# bot_uc_board.net
KiCad netlist of a schematic drawn in EAGLE
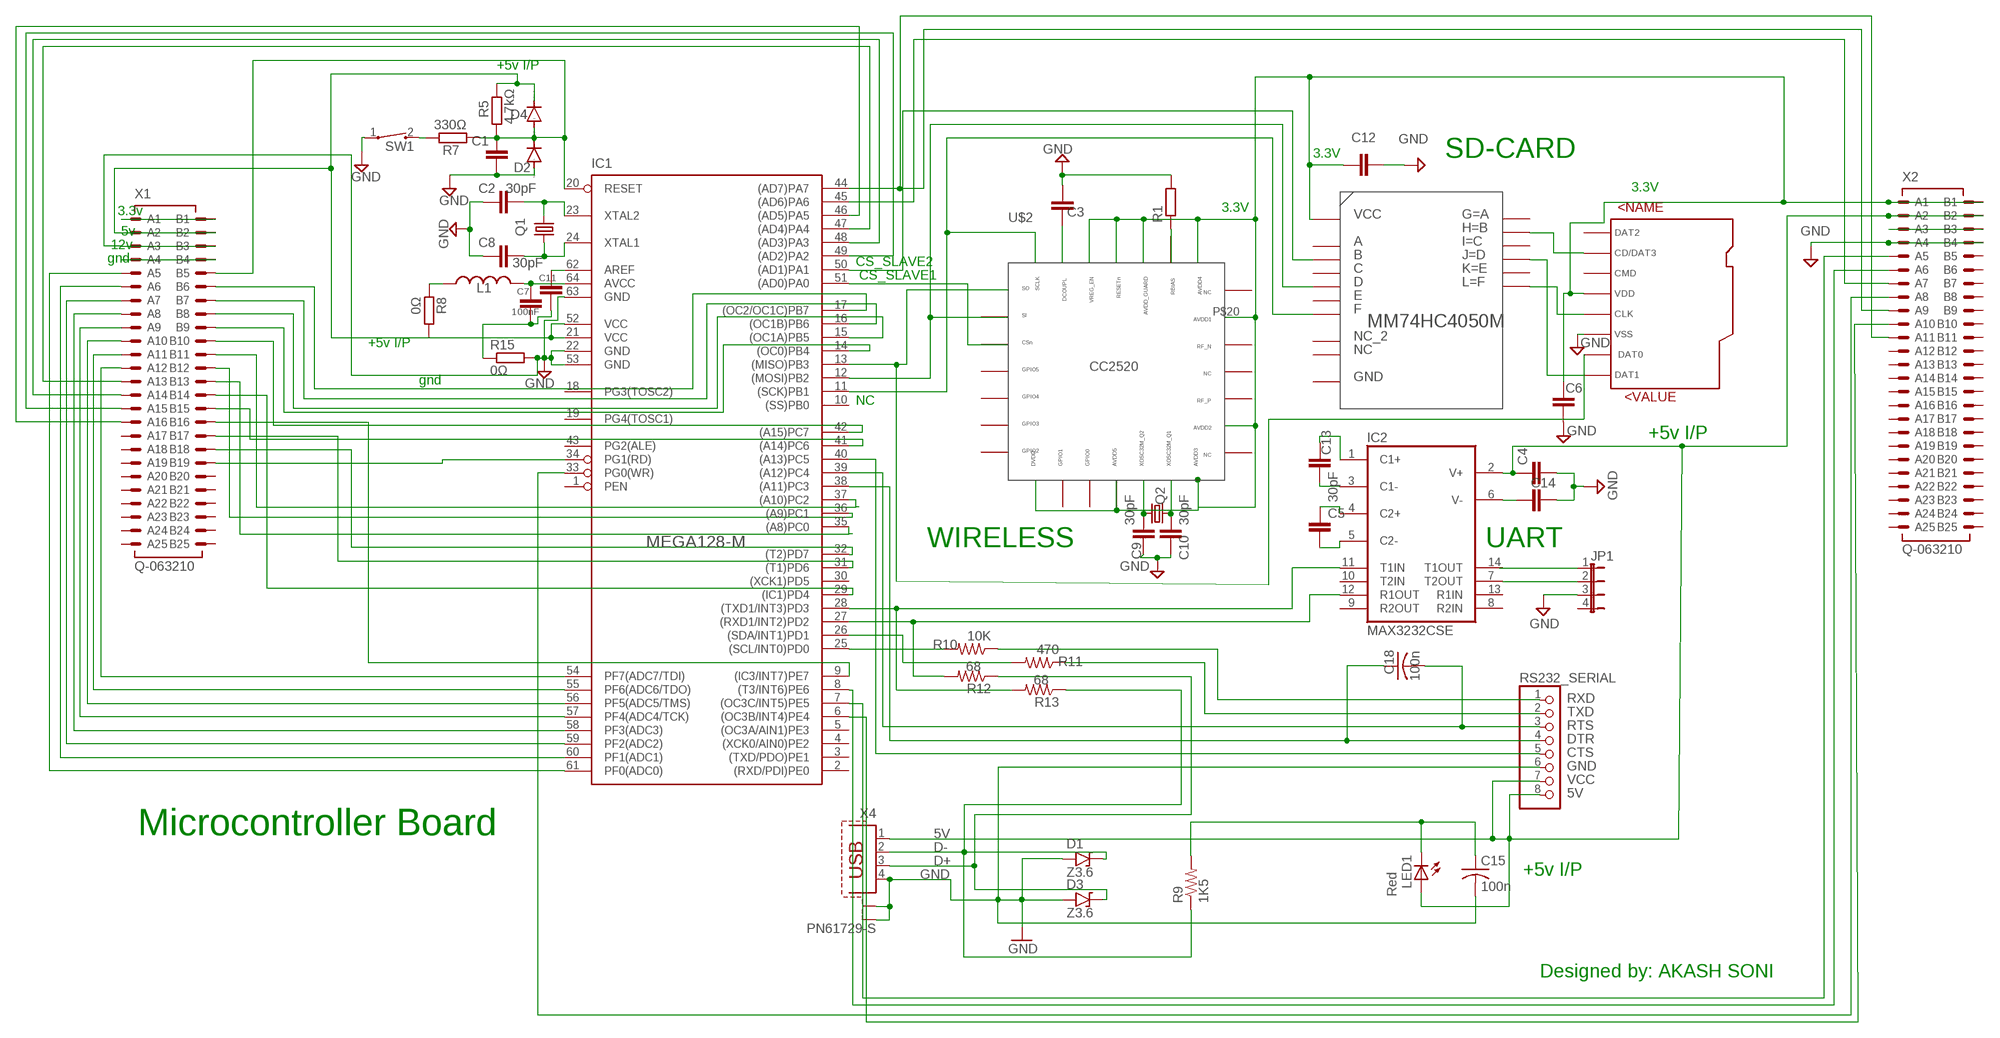
[diagram p0: schematic, sheet 1]

(export (version "E")
  (design (tool "Eeschema 10.0.6"))
  (components
    (comp (ref "C1")
      (value "C-EU025-024X044")
      (footprint "eagle-import:C025-024X044")
      (libsource (lib "eagle-import") (part "C-EU025-024X044"))
    )
    (comp (ref "C2")
      (value "30pF")
      (footprint "eagle-import:C025-024X044")
      (libsource (lib "eagle-import") (part "C-EU025-024X044"))
    )
    (comp (ref "C3")
      (value "C-EU025-024X044")
      (footprint "eagle-import:C025-024X044")
      (libsource (lib "eagle-import") (part "C-EU025-024X044"))
    )
    (comp (ref "C4")
      (value "C-EU025-024X044")
      (footprint "eagle-import:C025-024X044")
      (libsource (lib "eagle-import") (part "C-EU025-024X044"))
    )
    (comp (ref "C5")
      (value "C-EU025-024X044")
      (footprint "eagle-import:C025-024X044")
      (libsource (lib "eagle-import") (part "C-EU025-024X044"))
    )
    (comp (ref "C6")
      (value "30pF")
      (footprint "eagle-import:C025-024X044")
      (libsource (lib "eagle-import") (part "C-EU025-024X044"))
    )
    (comp (ref "C7")
      (value "C-EU025-024X044")
      (footprint "eagle-import:C025-024X044")
      (libsource (lib "eagle-import") (part "C-EU025-024X044"))
    )
    (comp (ref "C8")
      (value "30pF")
      (footprint "eagle-import:C025-024X044")
      (libsource (lib "eagle-import") (part "C-EU025-024X044"))
    )
    (comp (ref "C9")
      (value "30pF")
      (footprint "eagle-import:C025-024X044")
      (libsource (lib "eagle-import") (part "C-EU025-024X044"))
    )
    (comp (ref "C10")
      (value "30pF")
      (footprint "eagle-import:C025-024X044")
      (libsource (lib "eagle-import") (part "C-EU025-024X044"))
    )
    (comp (ref "C11")
      (value "100nF")
      (footprint "eagle-import:C025-024X044")
      (libsource (lib "eagle-import") (part "C-EU025-024X044"))
    )
    (comp (ref "C12")
      (value "C-EU025-024X044")
      (footprint "eagle-import:C025-024X044")
      (libsource (lib "eagle-import") (part "C-EU025-024X044"))
    )
    (comp (ref "C13")
      (value "30pF")
      (footprint "eagle-import:C025-024X044")
      (libsource (lib "eagle-import") (part "C-EU025-024X044"))
    )
    (comp (ref "C14")
      (value "C-EU025-024X044")
      (footprint "eagle-import:C025-024X044")
      (libsource (lib "eagle-import") (part "C-EU025-024X044"))
    )
    (comp (ref "C15")
      (value "100n")
      (footprint "eagle-import:C050-024X044")
      (libsource (lib "eagle-import") (part "C-US050-024X044"))
    )
    (comp (ref "C18")
      (value "100n")
      (footprint "eagle-import:C050-024X044")
      (libsource (lib "eagle-import") (part "C-US050-024X044"))
    )
    (comp (ref "D1")
      (value "Z3.6")
      (footprint "eagle-import:DO35-3")
      (libsource (lib "eagle-import") (part "1N9ZENER"))
    )
    (comp (ref "D2")
      (value "1N4004")
      (footprint "eagle-import:DO41-10")
      (libsource (lib "eagle-import") (part "1N4004"))
    )
    (comp (ref "D3")
      (value "Z3.6")
      (footprint "eagle-import:DO35-3")
      (libsource (lib "eagle-import") (part "1N9ZENER"))
    )
    (comp (ref "D4")
      (value "1N4004")
      (footprint "eagle-import:DO41-10")
      (libsource (lib "eagle-import") (part "1N4004"))
    )
    (comp (ref "IC1")
      (value "MEGA128-M")
      (footprint "eagle-import:MLF64")
      (fields (field (name "MPN") "ATMEGA128-16MU"))
      (libsource (lib "eagle-import") (part "MEGA128-M"))
    )
    (comp (ref "IC2")
      (value "MAX3232CSE")
      (footprint "eagle-import:SO16")
      (libsource (lib "eagle-import") (part "MAX3232SEC"))
    )
    (comp (ref "JP1")
      (value "JP4E")
      (footprint "eagle-import:JP4")
      (libsource (lib "eagle-import") (part "JP4E"))
    )
    (comp (ref "L1")
      (value "L-US0204/5")
      (footprint "eagle-import:0204_5")
      (libsource (lib "eagle-import") (part "L-US0204/5"))
    )
    (comp (ref "LED1")
      (value "Red")
      (footprint "eagle-import:LED3MM")
      (libsource (lib "eagle-import") (part "LED3MM"))
    )
    (comp (ref "Q1")
      (value "CRYSTALHC49U-V")
      (footprint "eagle-import:HC49U-V")
      (libsource (lib "eagle-import") (part "CRYSTALHC49U-V"))
    )
    (comp (ref "Q2")
      (value "CRYSTALHC49U-V")
      (footprint "eagle-import:HC49U-V")
      (libsource (lib "eagle-import") (part "CRYSTALHC49U-V"))
    )
    (comp (ref "R1")
      (value "R-EU_0204/2V")
      (footprint "eagle-import:0204V")
      (libsource (lib "eagle-import") (part "R-EU_0204/2V"))
    )
    (comp (ref "R5")
      (value "4.7kΩ")
      (footprint "eagle-import:0204V")
      (libsource (lib "eagle-import") (part "R-EU_0204/2V"))
    )
    (comp (ref "R7")
      (value "330Ω")
      (footprint "eagle-import:0204V")
      (libsource (lib "eagle-import") (part "R-EU_0204/2V"))
    )
    (comp (ref "R8")
      (value "0Ω")
      (footprint "eagle-import:0204V")
      (libsource (lib "eagle-import") (part "R-EU_0204/2V"))
    )
    (comp (ref "R9")
      (value "1K5")
      (footprint "eagle-import:0207_7")
      (libsource (lib "eagle-import") (part "R-US_0207/7"))
    )
    (comp (ref "R10")
      (value "10K")
      (footprint "eagle-import:0207_7")
      (libsource (lib "eagle-import") (part "R-US_0207/7"))
    )
    (comp (ref "R11")
      (value "470")
      (footprint "eagle-import:0207_7")
      (libsource (lib "eagle-import") (part "R-US_0207/7"))
    )
    (comp (ref "R12")
      (value "68")
      (footprint "eagle-import:0207_7")
      (libsource (lib "eagle-import") (part "R-US_0207/7"))
    )
    (comp (ref "R13")
      (value "68")
      (footprint "eagle-import:0207_7")
      (libsource (lib "eagle-import") (part "R-US_0207/7"))
    )
    (comp (ref "R15")
      (value "0Ω")
      (footprint "eagle-import:0204V")
      (libsource (lib "eagle-import") (part "R-EU_0204/2V"))
    )
    (comp (ref "RS232_SERIAL")
      (value "PINHD-1X8/90")
      (footprint "eagle-import:1X08_90")
      (libsource (lib "eagle-import") (part "PINHD-1X8/90"))
    )
    (comp (ref "SW1")
      (value "CT10-XXXX-A2")
      (footprint "eagle-import:CT10-XXXX-A2")
      (libsource (lib "eagle-import") (part "CT10-XXXX-A2"))
    )
    (comp (ref "U$1")
      (value "74HC4050")
      (footprint "eagle-import:74HC405")
      (libsource (lib "eagle-import") (part "74HC4050"))
    )
    (comp (ref "U$2")
      (value "CC2520")
      (footprint "eagle-import:CC2520_FOOT")
      (libsource (lib "eagle-import") (part "CC2520"))
    )
    (comp (ref "U$3")
      (value "SDCARD")
      (footprint "eagle-import:SDCARD_FOOT")
      (libsource (lib "eagle-import") (part "SDCARD"))
    )
    (comp (ref "X1")
      (value "Q-063210")
      (footprint "eagle-import:063210")
      (libsource (lib "eagle-import") (part "Q-063210"))
    )
    (comp (ref "X2")
      (value "Q-063210")
      (footprint "eagle-import:063210")
      (libsource (lib "eagle-import") (part "Q-063210"))
    )
    (comp (ref "X4")
      (value "PN61729-S")
      (footprint "eagle-import:PN61729-S")
      (libsource (lib "eagle-import") (part "PN61729-S"))
    )
  )
  (nets
    (net (code "1") (name "/D+") (class "Default")
      (node (ref "D3") (pin "C") (pinfunction "C_C") (pintype "passive"))
      (node (ref "R12") (pin "1") (pinfunction "1_1") (pintype "passive"))
      (node (ref "X4") (pin "3") (pinfunction "3_3") (pintype "passive"))
    )
    (net (code "2") (name "/D-") (class "Default")
      (node (ref "D1") (pin "C") (pinfunction "C_C") (pintype "passive"))
      (node (ref "R13") (pin "1") (pinfunction "1_1") (pintype "passive"))
      (node (ref "R9") (pin "1") (pinfunction "1_1") (pintype "passive"))
      (node (ref "X4") (pin "2") (pinfunction "2_2") (pintype "passive"))
    )
    (net (code "3") (name "GND") (class "Default")
      (node (ref "C1") (pin "1") (pinfunction "1_1") (pintype "passive"))
      (node (ref "C10") (pin "1") (pinfunction "1_1") (pintype "passive"))
      (node (ref "C12") (pin "2") (pinfunction "2_2") (pintype "passive"))
      (node (ref "C14") (pin "2") (pinfunction "2_2") (pintype "passive"))
      (node (ref "C15") (pin "2") (pinfunction "2_2") (pintype "passive"))
      (node (ref "C2") (pin "1") (pinfunction "1_1") (pintype "passive"))
      (node (ref "C3") (pin "1") (pinfunction "1_1") (pintype "passive"))
      (node (ref "C4") (pin "2") (pinfunction "2_2") (pintype "passive"))
      (node (ref "C6") (pin "1") (pinfunction "1_1") (pintype "passive"))
      (node (ref "C8") (pin "1") (pinfunction "1_1") (pintype "passive"))
      (node (ref "C9") (pin "1") (pinfunction "1_1") (pintype "passive"))
      (node (ref "D1") (pin "A") (pinfunction "A_A") (pintype "passive"))
      (node (ref "D2") (pin "A") (pinfunction "A_A") (pintype "passive"))
      (node (ref "D3") (pin "A") (pinfunction "A_A") (pintype "passive"))
      (node (ref "IC1") (pin "22") (pinfunction "GND_22") (pintype "power_in"))
      (node (ref "IC1") (pin "53") (pinfunction "GND_53") (pintype "power_in"))
      (node (ref "IC1") (pin "63") (pinfunction "GND_63") (pintype "power_in"))
      (node (ref "JP1") (pin "3") (pinfunction "3_3") (pintype "passive"))
      (node (ref "R1") (pin "2") (pinfunction "2_2") (pintype "passive"))
      (node (ref "R15") (pin "2") (pinfunction "2_2") (pintype "passive"))
      (node (ref "RS232_SERIAL") (pin "6") (pinfunction "6_6") (pintype "passive"))
      (node (ref "SW1") (pin "1") (pinfunction "1_1") (pintype "passive"))
      (node (ref "U$3") (pin "P$6") (pinfunction "VSS_P$6") (pintype "bidirectional"))
      (node (ref "X1") (pin "A3") (pinfunction "A3_A3") (pintype "passive"))
      (node (ref "X1") (pin "B3") (pinfunction "B3_B3") (pintype "passive"))
      (node (ref "X2") (pin "A4") (pinfunction "A4_A4") (pintype "passive"))
      (node (ref "X2") (pin "B4") (pinfunction "B4_B4") (pintype "passive"))
      (node (ref "X4") (pin "4") (pinfunction "4_4") (pintype "passive"))
      (node (ref "X4") (pin "S1") (pinfunction "S1_S1") (pintype "passive"))
      (node (ref "X4") (pin "S2") (pinfunction "S2_S2") (pintype "passive"))
    )
    (net (code "4") (name "Net-(C3-Pad2)") (class "Default")
      (node (ref "C3") (pin "2") (pinfunction "2_2") (pintype "passive"))
      (node (ref "U$2") (pin "P$27") (pinfunction "P$27_P$27") (pintype "bidirectional"))
    )
    (net (code "5") (name "Net-(C9-Pad2)") (class "Default")
      (node (ref "C9") (pin "2") (pinfunction "2_2") (pintype "passive"))
      (node (ref "Q2") (pin "2") (pinfunction "2_2") (pintype "passive"))
      (node (ref "U$2") (pin "P$12") (pinfunction "P$12_P$12") (pintype "bidirectional"))
    )
    (net (code "6") (name "Net-(C10-Pad2)") (class "Default")
      (node (ref "C10") (pin "2") (pinfunction "2_2") (pintype "passive"))
      (node (ref "Q2") (pin "1") (pinfunction "1_1") (pintype "passive"))
      (node (ref "U$2") (pin "P$13") (pinfunction "P$13_P$13") (pintype "bidirectional"))
    )
    (net (code "7") (name "Net-(C11-Pad1)") (class "Default")
      (node (ref "C11") (pin "1") (pinfunction "1_1") (pintype "passive"))
      (node (ref "C7") (pin "2") (pinfunction "2_2") (pintype "passive"))
      (node (ref "R15") (pin "1") (pinfunction "1_1") (pintype "passive"))
    )
    (net (code "8") (name "Net-(D4-PadC)") (class "Default")
      (node (ref "D4") (pin "C") (pinfunction "C_C") (pintype "passive"))
      (node (ref "IC1") (pin "21") (pinfunction "VCC_21") (pintype "power_in"))
      (node (ref "IC1") (pin "52") (pinfunction "VCC_52") (pintype "power_in"))
      (node (ref "R5") (pin "2") (pinfunction "2_2") (pintype "passive"))
      (node (ref "R8") (pin "2") (pinfunction "2_2") (pintype "passive"))
    )
    (net (code "9") (name "Net-(IC1-(A8)PC0)") (class "Default")
      (node (ref "IC1") (pin "35") (pinfunction "(A8)PC0_35") (pintype "output"))
      (node (ref "X1") (pin "B13") (pinfunction "B13_B13") (pintype "passive"))
    )
    (net (code "10") (name "Net-(IC1-(A9)PC1)") (class "Default")
      (node (ref "IC1") (pin "36") (pinfunction "(A9)PC1_36") (pintype "output"))
      (node (ref "X1") (pin "B12") (pinfunction "B12_B12") (pintype "passive"))
    )
    (net (code "11") (name "Net-(IC1-(A10)PC2)") (class "Default")
      (node (ref "IC1") (pin "37") (pinfunction "(A10)PC2_37") (pintype "output"))
      (node (ref "X1") (pin "B11") (pinfunction "B11_B11") (pintype "passive"))
    )
    (net (code "12") (name "Net-(IC1-(A11)PC3)") (class "Default")
      (node (ref "C18") (pin "1") (pinfunction "1_1") (pintype "passive"))
      (node (ref "IC1") (pin "38") (pinfunction "(A11)PC3_38") (pintype "output"))
      (node (ref "RS232_SERIAL") (pin "4") (pinfunction "4_4") (pintype "passive"))
    )
    (net (code "13") (name "Net-(IC1-(A12)PC4)") (class "Default")
      (node (ref "C18") (pin "2") (pinfunction "2_2") (pintype "passive"))
      (node (ref "IC1") (pin "39") (pinfunction "(A12)PC4_39") (pintype "output"))
      (node (ref "RS232_SERIAL") (pin "3") (pinfunction "3_3") (pintype "passive"))
    )
    (net (code "14") (name "Net-(IC1-(A13)PC5)") (class "Default")
      (node (ref "IC1") (pin "40") (pinfunction "(A13)PC5_40") (pintype "output"))
      (node (ref "RS232_SERIAL") (pin "5") (pinfunction "5_5") (pintype "passive"))
    )
    (net (code "15") (name "Net-(IC1-(A14)PC6)") (class "Default")
      (node (ref "IC1") (pin "41") (pinfunction "(A14)PC6_41") (pintype "output"))
      (node (ref "X1") (pin "B15") (pinfunction "B15_B15") (pintype "passive"))
    )
    (net (code "16") (name "Net-(IC1-(A15)PC7)") (class "Default")
      (node (ref "IC1") (pin "42") (pinfunction "(A15)PC7_42") (pintype "output"))
      (node (ref "X1") (pin "B10") (pinfunction "B10_B10") (pintype "passive"))
    )
    (net (code "17") (name "Net-(IC1-(AD0)PA0)") (class "Default")
      (node (ref "IC1") (pin "51") (pinfunction "(AD0)PA0_51") (pintype "bidirectional"))
      (node (ref "U$2") (pin "P$3") (pinfunction "P$3_P$3") (pintype "bidirectional"))
    )
    (net (code "18") (name "Net-(IC1-(AD1)PA1)") (class "Default")
      (node (ref "IC1") (pin "50") (pinfunction "(AD1)PA1_50") (pintype "bidirectional"))
      (node (ref "U$1") (pin "P$5") (pinfunction "B_P$5") (pintype "bidirectional"))
    )
    (net (code "19") (name "Net-(IC1-(AD2)PA2)") (class "Default")
      (node (ref "IC1") (pin "49") (pinfunction "(AD2)PA2_49") (pintype "bidirectional"))
      (node (ref "X1") (pin "A15") (pinfunction "A15_A15") (pintype "passive"))
    )
    (net (code "20") (name "Net-(IC1-(AD3)PA3)") (class "Default")
      (node (ref "IC1") (pin "48") (pinfunction "(AD3)PA3_48") (pintype "bidirectional"))
      (node (ref "X1") (pin "A14") (pinfunction "A14_A14") (pintype "passive"))
    )
    (net (code "21") (name "Net-(IC1-(AD4)PA4)") (class "Default")
      (node (ref "IC1") (pin "47") (pinfunction "(AD4)PA4_47") (pintype "bidirectional"))
      (node (ref "X1") (pin "A13") (pinfunction "A13_A13") (pintype "passive"))
    )
    (net (code "22") (name "Net-(IC1-(AD5)PA5)") (class "Default")
      (node (ref "IC1") (pin "46") (pinfunction "(AD5)PA5_46") (pintype "bidirectional"))
      (node (ref "X1") (pin "A16") (pinfunction "A16_A16") (pintype "passive"))
    )
    (net (code "23") (name "Net-(IC1-(AD6)PA6)") (class "Default")
      (node (ref "IC1") (pin "45") (pinfunction "(AD6)PA6_45") (pintype "bidirectional"))
      (node (ref "X2") (pin "A7") (pinfunction "A7_A7") (pintype "passive"))
    )
    (net (code "24") (name "Net-(IC1-(AD7)PA7)") (class "Default")
      (node (ref "IC1") (pin "44") (pinfunction "(AD7)PA7_44") (pintype "bidirectional"))
      (node (ref "X2") (pin "A11") (pinfunction "A11_A11") (pintype "passive"))
      (node (ref "X2") (pin "A9") (pinfunction "A9_A9") (pintype "passive"))
    )
    (net (code "25") (name "Net-(IC1-(IC1)PD4)") (class "Default")
      (node (ref "IC1") (pin "29") (pinfunction "(IC1)PD4_29") (pintype "bidirectional"))
      (node (ref "X1") (pin "B14") (pinfunction "B14_B14") (pintype "passive"))
    )
    (net (code "26") (name "Net-(IC1-(IC3{slash}INT7)PE7)") (class "Default")
      (node (ref "IC1") (pin "9") (pinfunction "(IC3/INT7)PE7_9") (pintype "bidirectional"))
      (node (ref "X1") (pin "B16") (pinfunction "B16_B16") (pintype "passive"))
    )
    (net (code "27") (name "Net-(IC1-(MISO)PB3)") (class "Default")
      (node (ref "IC1") (pin "13") (pinfunction "(MISO)PB3_13") (pintype "bidirectional"))
      (node (ref "U$2") (pin "P$1") (pinfunction "P$1_P$1") (pintype "bidirectional"))
      (node (ref "U$3") (pin "P$7") (pinfunction "DAT0_P$7") (pintype "bidirectional"))
    )
    (net (code "28") (name "Net-(IC1-(MOSI)PB2)") (class "Default")
      (node (ref "IC1") (pin "12") (pinfunction "(MOSI)PB2_12") (pintype "bidirectional"))
      (node (ref "U$1") (pin "P$9") (pinfunction "D_P$9") (pintype "bidirectional"))
      (node (ref "U$2") (pin "P$2") (pinfunction "P$2_P$2") (pintype "bidirectional"))
    )
    (net (code "29") (name "Net-(IC1-(OC0)PB4)") (class "Default")
      (node (ref "IC1") (pin "14") (pinfunction "(OC0)PB4_14") (pintype "bidirectional"))
      (node (ref "X1") (pin "B9") (pinfunction "B9_B9") (pintype "passive"))
    )
    (net (code "30") (name "Net-(IC1-(OC1A)PB5)") (class "Default")
      (node (ref "IC1") (pin "15") (pinfunction "(OC1A)PB5_15") (pintype "bidirectional"))
      (node (ref "X1") (pin "B8") (pinfunction "B8_B8") (pintype "passive"))
    )
    (net (code "31") (name "Net-(IC1-(OC1B)PB6)") (class "Default")
      (node (ref "IC1") (pin "16") (pinfunction "(OC1B)PB6_16") (pintype "bidirectional"))
      (node (ref "X1") (pin "B7") (pinfunction "B7_B7") (pintype "passive"))
    )
    (net (code "32") (name "Net-(IC1-(OC2{slash}OC1C)PB7)") (class "Default")
      (node (ref "IC1") (pin "17") (pinfunction "(OC2/OC1C)PB7_17") (pintype "bidirectional"))
      (node (ref "X1") (pin "B6") (pinfunction "B6_B6") (pintype "passive"))
    )
    (net (code "33") (name "Net-(IC1-(OC3B{slash}INT4)PE4)") (class "Default")
      (node (ref "IC1") (pin "6") (pinfunction "(OC3B/INT4)PE4_6") (pintype "bidirectional"))
      (node (ref "X2") (pin "A10") (pinfunction "A10_A10") (pintype "passive"))
    )
    (net (code "34") (name "Net-(IC1-(OC3C{slash}INT5)PE5)") (class "Default")
      (node (ref "IC1") (pin "7") (pinfunction "(OC3C/INT5)PE5_7") (pintype "bidirectional"))
      (node (ref "X2") (pin "A5") (pinfunction "A5_A5") (pintype "passive"))
    )
    (net (code "35") (name "Net-(IC1-(RXD1{slash}INT2)PD2)") (class "Default")
      (node (ref "IC1") (pin "27") (pinfunction "(RXD1/INT2)PD2_27") (pintype "bidirectional"))
      (node (ref "IC2") (pin "12") (pinfunction "R1OUT_12") (pintype "output"))
      (node (ref "R12") (pin "2") (pinfunction "2_2") (pintype "passive"))
    )
    (net (code "36") (name "Net-(IC1-(SCK)PB1)") (class "Default")
      (node (ref "IC1") (pin "11") (pinfunction "(SCK)PB1_11") (pintype "bidirectional"))
      (node (ref "U$1") (pin "P$14") (pinfunction "F_P$14") (pintype "bidirectional"))
      (node (ref "U$2") (pin "P$28") (pinfunction "P$28_P$28") (pintype "bidirectional"))
    )
    (net (code "37") (name "Net-(IC1-(SCL{slash}INT0)PD0)") (class "Default")
      (node (ref "IC1") (pin "25") (pinfunction "(SCL/INT0)PD0_25") (pintype "bidirectional"))
      (node (ref "R10") (pin "2") (pinfunction "2_2") (pintype "passive"))
    )
    (net (code "38") (name "Net-(IC1-(SDA{slash}INT1)PD1)") (class "Default")
      (node (ref "IC1") (pin "26") (pinfunction "(SDA/INT1)PD1_26") (pintype "bidirectional"))
      (node (ref "R11") (pin "2") (pinfunction "2_2") (pintype "passive"))
    )
    (net (code "39") (name "Net-(IC1-(T1)PD6)") (class "Default")
      (node (ref "IC1") (pin "31") (pinfunction "(T1)PD6_31") (pintype "bidirectional"))
      (node (ref "X1") (pin "B17") (pinfunction "B17_B17") (pintype "passive"))
    )
    (net (code "40") (name "Net-(IC1-(T2)PD7)") (class "Default")
      (node (ref "IC1") (pin "32") (pinfunction "(T2)PD7_32") (pintype "bidirectional"))
      (node (ref "X1") (pin "B18") (pinfunction "B18_B18") (pintype "passive"))
    )
    (net (code "41") (name "Net-(IC1-(T3{slash}INT6)PE6)") (class "Default")
      (node (ref "IC1") (pin "8") (pinfunction "(T3/INT6)PE6_8") (pintype "bidirectional"))
      (node (ref "X2") (pin "A6") (pinfunction "A6_A6") (pintype "passive"))
    )
    (net (code "42") (name "Net-(IC1-(TXD1{slash}INT3)PD3)") (class "Default")
      (node (ref "IC1") (pin "28") (pinfunction "(TXD1/INT3)PD3_28") (pintype "bidirectional"))
      (node (ref "IC2") (pin "11") (pinfunction "T1IN_11") (pintype "input"))
      (node (ref "R13") (pin "2") (pinfunction "2_2") (pintype "passive"))
    )
    (net (code "43") (name "Net-(IC1-AREF)") (class "Default")
      (node (ref "C11") (pin "2") (pinfunction "2_2") (pintype "passive"))
      (node (ref "IC1") (pin "62") (pinfunction "AREF_62") (pintype "passive"))
    )
    (net (code "44") (name "Net-(IC1-AVCC)") (class "Default")
      (node (ref "C7") (pin "1") (pinfunction "1_1") (pintype "passive"))
      (node (ref "IC1") (pin "64") (pinfunction "AVCC_64") (pintype "power_in"))
      (node (ref "L1") (pin "1") (pinfunction "1_1") (pintype "passive"))
    )
    (net (code "45") (name "Net-(IC1-PF0(ADC0))") (class "Default")
      (node (ref "IC1") (pin "61") (pinfunction "PF0(ADC0)_61") (pintype "input"))
      (node (ref "X1") (pin "A5") (pinfunction "A5_A5") (pintype "passive"))
    )
    (net (code "46") (name "Net-(IC1-PF1(ADC1))") (class "Default")
      (node (ref "IC1") (pin "60") (pinfunction "PF1(ADC1)_60") (pintype "input"))
      (node (ref "X1") (pin "A6") (pinfunction "A6_A6") (pintype "passive"))
    )
    (net (code "47") (name "Net-(IC1-PF2(ADC2))") (class "Default")
      (node (ref "IC1") (pin "59") (pinfunction "PF2(ADC2)_59") (pintype "input"))
      (node (ref "X1") (pin "A7") (pinfunction "A7_A7") (pintype "passive"))
    )
    (net (code "48") (name "Net-(IC1-PF3(ADC3))") (class "Default")
      (node (ref "IC1") (pin "58") (pinfunction "PF3(ADC3)_58") (pintype "input"))
      (node (ref "X1") (pin "A8") (pinfunction "A8_A8") (pintype "passive"))
    )
    (net (code "49") (name "Net-(IC1-PF4(ADC4{slash}TCK))") (class "Default")
      (node (ref "IC1") (pin "57") (pinfunction "PF4(ADC4/TCK)_57") (pintype "input"))
      (node (ref "X1") (pin "A9") (pinfunction "A9_A9") (pintype "passive"))
    )
    (net (code "50") (name "Net-(IC1-PF5(ADC5{slash}TMS))") (class "Default")
      (node (ref "IC1") (pin "56") (pinfunction "PF5(ADC5/TMS)_56") (pintype "input"))
      (node (ref "X1") (pin "A10") (pinfunction "A10_A10") (pintype "passive"))
    )
    (net (code "51") (name "Net-(IC1-PF6(ADC6{slash}TDO))") (class "Default")
      (node (ref "IC1") (pin "55") (pinfunction "PF6(ADC6/TDO)_55") (pintype "input"))
      (node (ref "X1") (pin "A11") (pinfunction "A11_A11") (pintype "passive"))
    )
    (net (code "52") (name "Net-(IC1-PF7(ADC7{slash}TDI))") (class "Default")
      (node (ref "IC1") (pin "54") (pinfunction "PF7(ADC7/TDI)_54") (pintype "input"))
      (node (ref "X1") (pin "A12") (pinfunction "A12_A12") (pintype "passive"))
    )
    (net (code "53") (name "Net-(IC1-PG0(WR))") (class "Default")
      (node (ref "IC1") (pin "33") (pinfunction "PG0(WR)_33") (pintype "bidirectional"))
      (node (ref "X2") (pin "A8") (pinfunction "A8_A8") (pintype "passive"))
    )
    (net (code "54") (name "Net-(IC1-PG1(RD))") (class "Default")
      (node (ref "IC1") (pin "34") (pinfunction "PG1(RD)_34") (pintype "bidirectional"))
      (node (ref "X1") (pin "B19") (pinfunction "B19_B19") (pintype "passive"))
    )
    (net (code "55") (name "Net-(IC1-RESET)") (class "Default")
      (node (ref "D2") (pin "C") (pinfunction "C_C") (pintype "passive"))
      (node (ref "D4") (pin "A") (pinfunction "A_A") (pintype "passive"))
      (node (ref "IC1") (pin "20") (pinfunction "RESET_20") (pintype "input"))
      (node (ref "R5") (pin "1") (pinfunction "1_1") (pintype "passive"))
      (node (ref "R7") (pin "1") (pinfunction "1_1") (pintype "passive"))
      (node (ref "X1") (pin "B5") (pinfunction "B5_B5") (pintype "passive"))
    )
    (net (code "56") (name "Net-(IC1-XTAL1)") (class "Default")
      (node (ref "C8") (pin "2") (pinfunction "2_2") (pintype "passive"))
      (node (ref "IC1") (pin "24") (pinfunction "XTAL1_24") (pintype "bidirectional"))
      (node (ref "Q1") (pin "1") (pinfunction "1_1") (pintype "passive"))
    )
    (net (code "57") (name "Net-(IC1-XTAL2)") (class "Default")
      (node (ref "C2") (pin "2") (pinfunction "2_2") (pintype "passive"))
      (node (ref "IC1") (pin "23") (pinfunction "XTAL2_23") (pintype "bidirectional"))
      (node (ref "Q1") (pin "2") (pinfunction "2_2") (pintype "passive"))
    )
    (net (code "58") (name "Net-(IC2A-C1+)") (class "Default")
      (node (ref "C13") (pin "1") (pinfunction "1_1") (pintype "passive"))
      (node (ref "IC2") (pin "1") (pinfunction "C1+_1") (pintype "bidirectional"))
    )
    (net (code "59") (name "Net-(IC2A-C1-)") (class "Default")
      (node (ref "C13") (pin "2") (pinfunction "2_2") (pintype "passive"))
      (node (ref "IC2") (pin "3") (pinfunction "C1-_3") (pintype "bidirectional"))
    )
    (net (code "60") (name "Net-(IC2A-C2+)") (class "Default")
      (node (ref "C5") (pin "1") (pinfunction "1_1") (pintype "passive"))
      (node (ref "IC2") (pin "4") (pinfunction "C2+_4") (pintype "bidirectional"))
    )
    (net (code "61") (name "Net-(IC2A-C2-)") (class "Default")
      (node (ref "C5") (pin "2") (pinfunction "2_2") (pintype "passive"))
      (node (ref "IC2") (pin "5") (pinfunction "C2-_5") (pintype "bidirectional"))
    )
    (net (code "62") (name "Net-(IC2A-T1OUT)") (class "Default")
      (node (ref "IC2") (pin "14") (pinfunction "T1OUT_14") (pintype "output"))
      (node (ref "JP1") (pin "1") (pinfunction "1_1") (pintype "passive"))
    )
    (net (code "63") (name "Net-(IC2A-T2OUT)") (class "Default")
      (node (ref "IC2") (pin "7") (pinfunction "T2OUT_7") (pintype "output"))
      (node (ref "JP1") (pin "2") (pinfunction "2_2") (pintype "passive"))
    )
    (net (code "64") (name "Net-(IC2A-V+)") (class "Default")
      (node (ref "C4") (pin "1") (pinfunction "1_1") (pintype "passive"))
      (node (ref "IC2") (pin "2") (pinfunction "V+_2") (pintype "bidirectional"))
      (node (ref "LED1") (pin "A") (pinfunction "A_A") (pintype "passive"))
      (node (ref "RS232_SERIAL") (pin "7") (pinfunction "7_7") (pintype "passive"))
      (node (ref "RS232_SERIAL") (pin "8") (pinfunction "8_8") (pintype "passive"))
      (node (ref "X2") (pin "A2") (pinfunction "A2_A2") (pintype "passive"))
      (node (ref "X2") (pin "B2") (pinfunction "B2_B2") (pintype "passive"))
      (node (ref "X4") (pin "1") (pinfunction "1_1") (pintype "passive"))
    )
    (net (code "65") (name "Net-(IC2A-V-)") (class "Default")
      (node (ref "C14") (pin "1") (pinfunction "1_1") (pintype "passive"))
      (node (ref "IC2") (pin "6") (pinfunction "V-_6") (pintype "bidirectional"))
    )
    (net (code "66") (name "Net-(L1-Pad2)") (class "Default")
      (node (ref "L1") (pin "2") (pinfunction "2_2") (pintype "passive"))
      (node (ref "R8") (pin "1") (pinfunction "1_1") (pintype "passive"))
    )
    (net (code "67") (name "Net-(LED1-C)") (class "Default")
      (node (ref "C15") (pin "1") (pinfunction "1_1") (pintype "passive"))
      (node (ref "LED1") (pin "K") (pinfunction "C_K") (pintype "passive"))
      (node (ref "R9") (pin "2") (pinfunction "2_2") (pintype "passive"))
    )
    (net (code "68") (name "Net-(R1-Pad1)") (class "Default")
      (node (ref "R1") (pin "1") (pinfunction "1_1") (pintype "passive"))
      (node (ref "U$2") (pin "P$23") (pinfunction "P$23_P$23") (pintype "bidirectional"))
    )
    (net (code "69") (name "Net-(R7-Pad2)") (class "Default")
      (node (ref "R7") (pin "2") (pinfunction "2_2") (pintype "passive"))
      (node (ref "SW1") (pin "2") (pinfunction "2_2") (pintype "passive"))
    )
    (net (code "70") (name "Net-(R10-Pad1)") (class "Default")
      (node (ref "R10") (pin "1") (pinfunction "1_1") (pintype "passive"))
      (node (ref "RS232_SERIAL") (pin "1") (pinfunction "1_1") (pintype "passive"))
    )
    (net (code "71") (name "Net-(R11-Pad1)") (class "Default")
      (node (ref "R11") (pin "1") (pinfunction "1_1") (pintype "passive"))
      (node (ref "RS232_SERIAL") (pin "2") (pinfunction "2_2") (pintype "passive"))
    )
    (net (code "72") (name "Net-(U$1-H)") (class "Default")
      (node (ref "U$1") (pin "P$4") (pinfunction "H_P$4") (pintype "bidirectional"))
      (node (ref "U$3") (pin "P$2") (pinfunction "CD/DAT3_P$2") (pintype "bidirectional"))
    )
    (net (code "73") (name "Net-(U$1-J)") (class "Default")
      (node (ref "U$1") (pin "P$10") (pinfunction "J_P$10") (pintype "bidirectional"))
      (node (ref "U$3") (pin "P$8") (pinfunction "DAT1_P$8") (pintype "bidirectional"))
    )
    (net (code "74") (name "Net-(U$1-L)") (class "Default")
      (node (ref "U$1") (pin "P$15") (pinfunction "L_P$15") (pintype "bidirectional"))
      (node (ref "U$3") (pin "P$5") (pinfunction "CLK_P$5") (pintype "bidirectional"))
    )
    (net (code "75") (name "Net-(U$1-VCC)") (class "Default")
      (node (ref "C12") (pin "1") (pinfunction "1_1") (pintype "passive"))
      (node (ref "C6") (pin "2") (pinfunction "2_2") (pintype "passive"))
      (node (ref "U$1") (pin "P$1") (pinfunction "VCC_P$1") (pintype "bidirectional"))
      (node (ref "U$2") (pin "P$11") (pinfunction "P$11_P$11") (pintype "bidirectional"))
      (node (ref "U$2") (pin "P$14") (pinfunction "P$14_P$14") (pintype "bidirectional"))
      (node (ref "U$2") (pin "P$16") (pinfunction "P$16_P$16") (pintype "bidirectional"))
      (node (ref "U$2") (pin "P$20") (pinfunction "P$20_P$20") (pintype "bidirectional"))
      (node (ref "U$2") (pin "P$22") (pinfunction "P$22_P$22") (pintype "bidirectional"))
      (node (ref "U$2") (pin "P$24") (pinfunction "P$24_P$24") (pintype "bidirectional"))
      (node (ref "U$2") (pin "P$25") (pinfunction "P$25_P$25") (pintype "bidirectional"))
      (node (ref "U$2") (pin "P$26") (pinfunction "P$26_P$26") (pintype "bidirectional"))
      (node (ref "U$2") (pin "P$8") (pinfunction "P$8_P$8") (pintype "bidirectional"))
      (node (ref "U$3") (pin "P$4") (pinfunction "VDD_P$4") (pintype "bidirectional"))
      (node (ref "X2") (pin "A1") (pinfunction "A1_A1") (pintype "passive"))
      (node (ref "X2") (pin "B1") (pinfunction "B1_B1") (pintype "passive"))
    )
    (net (code "76") (name "Net-(X1-PadA1)") (class "Default")
      (node (ref "X1") (pin "A1") (pinfunction "A1_A1") (pintype "passive"))
      (node (ref "X1") (pin "B1") (pinfunction "B1_B1") (pintype "passive"))
    )
    (net (code "77") (name "Net-(X1-PadA2)") (class "Default")
      (node (ref "X1") (pin "A2") (pinfunction "A2_A2") (pintype "passive"))
      (node (ref "X1") (pin "B2") (pinfunction "B2_B2") (pintype "passive"))
    )
    (net (code "78") (name "Net-(X1-PadA4)") (class "Default")
      (node (ref "X1") (pin "A4") (pinfunction "A4_A4") (pintype "passive"))
      (node (ref "X1") (pin "B4") (pinfunction "B4_B4") (pintype "passive"))
    )
    (net (code "79") (name "Net-(X2-PadA3)") (class "Default")
      (node (ref "X2") (pin "A3") (pinfunction "A3_A3") (pintype "passive"))
      (node (ref "X2") (pin "B3") (pinfunction "B3_B3") (pintype "passive"))
    )
    (net (code "80") (name "unconnected-(C1-Pad2)") (class "Default")
      (node (ref "C1") (pin "2") (pinfunction "2_2") (pintype "passive"))
    )
    (net (code "81") (name "unconnected-(IC1-(OC3A{slash}AIN1)PE3-Pad5)") (class "Default")
      (node (ref "IC1") (pin "5") (pinfunction "(OC3A/AIN1)PE3_5") (pintype "bidirectional"))
    )
    (net (code "82") (name "unconnected-(IC1-(RXD{slash}PDI)PE0-Pad2)") (class "Default")
      (node (ref "IC1") (pin "2") (pinfunction "(RXD/PDI)PE0_2") (pintype "bidirectional"))
    )
    (net (code "83") (name "unconnected-(IC1-(SS)PB0-Pad10)") (class "Default")
      (node (ref "IC1") (pin "10") (pinfunction "(SS)PB0_10") (pintype "bidirectional"))
    )
    (net (code "84") (name "unconnected-(IC1-(TXD{slash}PDO)PE1-Pad3)") (class "Default")
      (node (ref "IC1") (pin "3") (pinfunction "(TXD/PDO)PE1_3") (pintype "bidirectional"))
    )
    (net (code "85") (name "unconnected-(IC1-(XCK0{slash}AIN0)PE2-Pad4)") (class "Default")
      (node (ref "IC1") (pin "4") (pinfunction "(XCK0/AIN0)PE2_4") (pintype "bidirectional"))
    )
    (net (code "86") (name "unconnected-(IC1-(XCK1)PD5-Pad30)") (class "Default")
      (node (ref "IC1") (pin "30") (pinfunction "(XCK1)PD5_30") (pintype "bidirectional"))
    )
    (net (code "87") (name "unconnected-(IC1-PEN-Pad1)") (class "Default")
      (node (ref "IC1") (pin "1") (pinfunction "PEN_1") (pintype "input"))
    )
    (net (code "88") (name "unconnected-(IC1-PG2(ALE)-Pad43)") (class "Default")
      (node (ref "IC1") (pin "43") (pinfunction "PG2(ALE)_43") (pintype "bidirectional"))
    )
    (net (code "89") (name "unconnected-(IC1-PG3(TOSC2)-Pad18)") (class "Default")
      (node (ref "IC1") (pin "18") (pinfunction "PG3(TOSC2)_18") (pintype "bidirectional"))
    )
    (net (code "90") (name "unconnected-(IC1-PG4(TOSC1)-Pad19)") (class "Default")
      (node (ref "IC1") (pin "19") (pinfunction "PG4(TOSC1)_19") (pintype "bidirectional"))
    )
    (net (code "91") (name "unconnected-(IC2A-R1IN-Pad13)") (class "Default")
      (node (ref "IC2") (pin "13") (pinfunction "R1IN_13") (pintype "input"))
    )
    (net (code "92") (name "unconnected-(IC2A-R2IN-Pad8)") (class "Default")
      (node (ref "IC2") (pin "8") (pinfunction "R2IN_8") (pintype "input"))
    )
    (net (code "93") (name "unconnected-(IC2A-R2OUT-Pad9)") (class "Default")
      (node (ref "IC2") (pin "9") (pinfunction "R2OUT_9") (pintype "output"))
    )
    (net (code "94") (name "unconnected-(IC2A-T2IN-Pad10)") (class "Default")
      (node (ref "IC2") (pin "10") (pinfunction "T2IN_10") (pintype "input"))
    )
    (net (code "95") (name "unconnected-(JP1-Pad4)") (class "Default")
      (node (ref "JP1") (pin "4") (pinfunction "4_4") (pintype "passive"))
    )
    (net (code "96") (name "unconnected-(U$1-A-PadP$3)") (class "Default")
      (node (ref "U$1") (pin "P$3") (pinfunction "A_P$3") (pintype "bidirectional"))
    )
    (net (code "97") (name "unconnected-(U$1-C-PadP$7)") (class "Default")
      (node (ref "U$1") (pin "P$7") (pinfunction "C_P$7") (pintype "bidirectional"))
    )
    (net (code "98") (name "unconnected-(U$1-E-PadP$11)") (class "Default")
      (node (ref "U$1") (pin "P$11") (pinfunction "E_P$11") (pintype "bidirectional"))
    )
    (net (code "99") (name "unconnected-(U$1-G-PadP$2)") (class "Default")
      (node (ref "U$1") (pin "P$2") (pinfunction "G_P$2") (pintype "bidirectional"))
    )
    (net (code "100") (name "unconnected-(U$1-GND-PadP$8)") (class "Default")
      (node (ref "U$1") (pin "P$8") (pinfunction "GND_P$8") (pintype "bidirectional"))
    )
    (net (code "101") (name "unconnected-(U$1-I-PadP$6)") (class "Default")
      (node (ref "U$1") (pin "P$6") (pinfunction "I_P$6") (pintype "bidirectional"))
    )
    (net (code "102") (name "unconnected-(U$1-K-PadP$12)") (class "Default")
      (node (ref "U$1") (pin "P$12") (pinfunction "K_P$12") (pintype "bidirectional"))
    )
    (net (code "103") (name "unconnected-(U$1-NC-PadP$16)") (class "Default")
      (node (ref "U$1") (pin "P$16") (pinfunction "NC_P$16") (pintype "bidirectional"))
    )
    (net (code "104") (name "unconnected-(U$1-NC_2-PadP$13)") (class "Default")
      (node (ref "U$1") (pin "P$13") (pinfunction "NC_2_P$13") (pintype "bidirectional"))
    )
    (net (code "105") (name "unconnected-(U$2-PadP$4)") (class "Default")
      (node (ref "U$2") (pin "P$4") (pinfunction "P$4_P$4") (pintype "bidirectional"))
    )
    (net (code "106") (name "unconnected-(U$2-PadP$5)") (class "Default")
      (node (ref "U$2") (pin "P$5") (pinfunction "P$5_P$5") (pintype "bidirectional"))
    )
    (net (code "107") (name "unconnected-(U$2-PadP$6)") (class "Default")
      (node (ref "U$2") (pin "P$6") (pinfunction "P$6_P$6") (pintype "bidirectional"))
    )
    (net (code "108") (name "unconnected-(U$2-PadP$7)") (class "Default")
      (node (ref "U$2") (pin "P$7") (pinfunction "P$7_P$7") (pintype "bidirectional"))
    )
    (net (code "109") (name "unconnected-(U$2-PadP$9)") (class "Default")
      (node (ref "U$2") (pin "P$9") (pinfunction "P$9_P$9") (pintype "bidirectional"))
    )
    (net (code "110") (name "unconnected-(U$2-PadP$10)") (class "Default")
      (node (ref "U$2") (pin "P$10") (pinfunction "P$10_P$10") (pintype "bidirectional"))
    )
    (net (code "111") (name "unconnected-(U$2-PadP$15)") (class "Default")
      (node (ref "U$2") (pin "P$15") (pinfunction "P$15_P$15") (pintype "bidirectional"))
    )
    (net (code "112") (name "unconnected-(U$2-PadP$17)") (class "Default")
      (node (ref "U$2") (pin "P$17") (pinfunction "P$17_P$17") (pintype "bidirectional"))
    )
    (net (code "113") (name "unconnected-(U$2-PadP$18)") (class "Default")
      (node (ref "U$2") (pin "P$18") (pinfunction "P$18_P$18") (pintype "bidirectional"))
    )
    (net (code "114") (name "unconnected-(U$2-PadP$19)") (class "Default")
      (node (ref "U$2") (pin "P$19") (pinfunction "P$19_P$19") (pintype "bidirectional"))
    )
    (net (code "115") (name "unconnected-(U$2-PadP$21)") (class "Default")
      (node (ref "U$2") (pin "P$21") (pinfunction "P$21_P$21") (pintype "bidirectional"))
    )
    (net (code "116") (name "unconnected-(U$3-CMD-PadP$3)") (class "Default")
      (node (ref "U$3") (pin "P$3") (pinfunction "CMD_P$3") (pintype "bidirectional"))
    )
    (net (code "117") (name "unconnected-(U$3-DAT2-PadP$1)") (class "Default")
      (node (ref "U$3") (pin "P$1") (pinfunction "DAT2_P$1") (pintype "bidirectional"))
    )
    (net (code "118") (name "unconnected-(X1-PadA17)") (class "Default")
      (node (ref "X1") (pin "A17") (pinfunction "A17_A17") (pintype "passive"))
    )
    (net (code "119") (name "unconnected-(X1-PadA18)") (class "Default")
      (node (ref "X1") (pin "A18") (pinfunction "A18_A18") (pintype "passive"))
    )
    (net (code "120") (name "unconnected-(X1-PadA19)") (class "Default")
      (node (ref "X1") (pin "A19") (pinfunction "A19_A19") (pintype "passive"))
    )
    (net (code "121") (name "unconnected-(X1-PadA20)") (class "Default")
      (node (ref "X1") (pin "A20") (pinfunction "A20_A20") (pintype "passive"))
    )
    (net (code "122") (name "unconnected-(X1-PadA21)") (class "Default")
      (node (ref "X1") (pin "A21") (pinfunction "A21_A21") (pintype "passive"))
    )
    (net (code "123") (name "unconnected-(X1-PadA22)") (class "Default")
      (node (ref "X1") (pin "A22") (pinfunction "A22_A22") (pintype "passive"))
    )
    (net (code "124") (name "unconnected-(X1-PadA23)") (class "Default")
      (node (ref "X1") (pin "A23") (pinfunction "A23_A23") (pintype "passive"))
    )
    (net (code "125") (name "unconnected-(X1-PadA24)") (class "Default")
      (node (ref "X1") (pin "A24") (pinfunction "A24_A24") (pintype "passive"))
    )
    (net (code "126") (name "unconnected-(X1-PadA25)") (class "Default")
      (node (ref "X1") (pin "A25") (pinfunction "A25_A25") (pintype "passive"))
    )
    (net (code "127") (name "unconnected-(X1-PadB20)") (class "Default")
      (node (ref "X1") (pin "B20") (pinfunction "B20_B20") (pintype "passive"))
    )
    (net (code "128") (name "unconnected-(X1-PadB21)") (class "Default")
      (node (ref "X1") (pin "B21") (pinfunction "B21_B21") (pintype "passive"))
    )
    (net (code "129") (name "unconnected-(X1-PadB22)") (class "Default")
      (node (ref "X1") (pin "B22") (pinfunction "B22_B22") (pintype "passive"))
    )
    (net (code "130") (name "unconnected-(X1-PadB23)") (class "Default")
      (node (ref "X1") (pin "B23") (pinfunction "B23_B23") (pintype "passive"))
    )
    (net (code "131") (name "unconnected-(X1-PadB24)") (class "Default")
      (node (ref "X1") (pin "B24") (pinfunction "B24_B24") (pintype "passive"))
    )
    (net (code "132") (name "unconnected-(X1-PadB25)") (class "Default")
      (node (ref "X1") (pin "B25") (pinfunction "B25_B25") (pintype "passive"))
    )
    (net (code "133") (name "unconnected-(X2-PadA12)") (class "Default")
      (node (ref "X2") (pin "A12") (pinfunction "A12_A12") (pintype "passive"))
    )
    (net (code "134") (name "unconnected-(X2-PadA13)") (class "Default")
      (node (ref "X2") (pin "A13") (pinfunction "A13_A13") (pintype "passive"))
    )
    (net (code "135") (name "unconnected-(X2-PadA14)") (class "Default")
      (node (ref "X2") (pin "A14") (pinfunction "A14_A14") (pintype "passive"))
    )
    (net (code "136") (name "unconnected-(X2-PadA15)") (class "Default")
      (node (ref "X2") (pin "A15") (pinfunction "A15_A15") (pintype "passive"))
    )
    (net (code "137") (name "unconnected-(X2-PadA16)") (class "Default")
      (node (ref "X2") (pin "A16") (pinfunction "A16_A16") (pintype "passive"))
    )
    (net (code "138") (name "unconnected-(X2-PadA17)") (class "Default")
      (node (ref "X2") (pin "A17") (pinfunction "A17_A17") (pintype "passive"))
    )
    (net (code "139") (name "unconnected-(X2-PadA18)") (class "Default")
      (node (ref "X2") (pin "A18") (pinfunction "A18_A18") (pintype "passive"))
    )
    (net (code "140") (name "unconnected-(X2-PadA19)") (class "Default")
      (node (ref "X2") (pin "A19") (pinfunction "A19_A19") (pintype "passive"))
    )
    (net (code "141") (name "unconnected-(X2-PadA20)") (class "Default")
      (node (ref "X2") (pin "A20") (pinfunction "A20_A20") (pintype "passive"))
    )
    (net (code "142") (name "unconnected-(X2-PadA21)") (class "Default")
      (node (ref "X2") (pin "A21") (pinfunction "A21_A21") (pintype "passive"))
    )
    (net (code "143") (name "unconnected-(X2-PadA22)") (class "Default")
      (node (ref "X2") (pin "A22") (pinfunction "A22_A22") (pintype "passive"))
    )
    (net (code "144") (name "unconnected-(X2-PadA23)") (class "Default")
      (node (ref "X2") (pin "A23") (pinfunction "A23_A23") (pintype "passive"))
    )
    (net (code "145") (name "unconnected-(X2-PadA24)") (class "Default")
      (node (ref "X2") (pin "A24") (pinfunction "A24_A24") (pintype "passive"))
    )
    (net (code "146") (name "unconnected-(X2-PadA25)") (class "Default")
      (node (ref "X2") (pin "A25") (pinfunction "A25_A25") (pintype "passive"))
    )
    (net (code "147") (name "unconnected-(X2-PadB5)") (class "Default")
      (node (ref "X2") (pin "B5") (pinfunction "B5_B5") (pintype "passive"))
    )
    (net (code "148") (name "unconnected-(X2-PadB6)") (class "Default")
      (node (ref "X2") (pin "B6") (pinfunction "B6_B6") (pintype "passive"))
    )
    (net (code "149") (name "unconnected-(X2-PadB7)") (class "Default")
      (node (ref "X2") (pin "B7") (pinfunction "B7_B7") (pintype "passive"))
    )
    (net (code "150") (name "unconnected-(X2-PadB8)") (class "Default")
      (node (ref "X2") (pin "B8") (pinfunction "B8_B8") (pintype "passive"))
    )
    (net (code "151") (name "unconnected-(X2-PadB9)") (class "Default")
      (node (ref "X2") (pin "B9") (pinfunction "B9_B9") (pintype "passive"))
    )
    (net (code "152") (name "unconnected-(X2-PadB10)") (class "Default")
      (node (ref "X2") (pin "B10") (pinfunction "B10_B10") (pintype "passive"))
    )
    (net (code "153") (name "unconnected-(X2-PadB11)") (class "Default")
      (node (ref "X2") (pin "B11") (pinfunction "B11_B11") (pintype "passive"))
    )
    (net (code "154") (name "unconnected-(X2-PadB12)") (class "Default")
      (node (ref "X2") (pin "B12") (pinfunction "B12_B12") (pintype "passive"))
    )
    (net (code "155") (name "unconnected-(X2-PadB13)") (class "Default")
      (node (ref "X2") (pin "B13") (pinfunction "B13_B13") (pintype "passive"))
    )
    (net (code "156") (name "unconnected-(X2-PadB14)") (class "Default")
      (node (ref "X2") (pin "B14") (pinfunction "B14_B14") (pintype "passive"))
    )
    (net (code "157") (name "unconnected-(X2-PadB15)") (class "Default")
      (node (ref "X2") (pin "B15") (pinfunction "B15_B15") (pintype "passive"))
    )
    (net (code "158") (name "unconnected-(X2-PadB16)") (class "Default")
      (node (ref "X2") (pin "B16") (pinfunction "B16_B16") (pintype "passive"))
    )
    (net (code "159") (name "unconnected-(X2-PadB17)") (class "Default")
      (node (ref "X2") (pin "B17") (pinfunction "B17_B17") (pintype "passive"))
    )
    (net (code "160") (name "unconnected-(X2-PadB18)") (class "Default")
      (node (ref "X2") (pin "B18") (pinfunction "B18_B18") (pintype "passive"))
    )
    (net (code "161") (name "unconnected-(X2-PadB19)") (class "Default")
      (node (ref "X2") (pin "B19") (pinfunction "B19_B19") (pintype "passive"))
    )
    (net (code "162") (name "unconnected-(X2-PadB20)") (class "Default")
      (node (ref "X2") (pin "B20") (pinfunction "B20_B20") (pintype "passive"))
    )
    (net (code "163") (name "unconnected-(X2-PadB21)") (class "Default")
      (node (ref "X2") (pin "B21") (pinfunction "B21_B21") (pintype "passive"))
    )
    (net (code "164") (name "unconnected-(X2-PadB22)") (class "Default")
      (node (ref "X2") (pin "B22") (pinfunction "B22_B22") (pintype "passive"))
    )
    (net (code "165") (name "unconnected-(X2-PadB23)") (class "Default")
      (node (ref "X2") (pin "B23") (pinfunction "B23_B23") (pintype "passive"))
    )
    (net (code "166") (name "unconnected-(X2-PadB24)") (class "Default")
      (node (ref "X2") (pin "B24") (pinfunction "B24_B24") (pintype "passive"))
    )
    (net (code "167") (name "unconnected-(X2-PadB25)") (class "Default")
      (node (ref "X2") (pin "B25") (pinfunction "B25_B25") (pintype "passive"))
    )
  )
)
